# Sheet2_3.net
KiCad netlist of a schematic drawn in Altium Designer
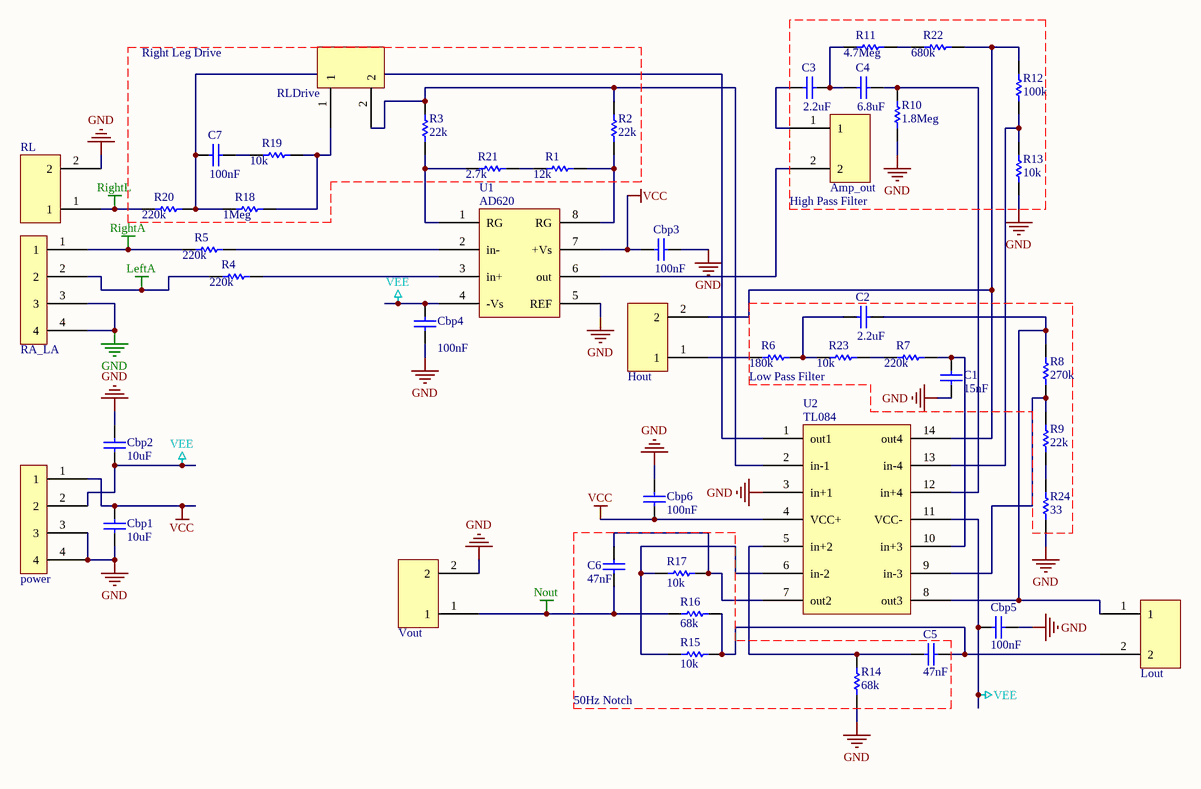
[diagram p0: Sheet2.~(3).SchDoc]

(export (version "E")
  (design (tool "Eeschema 10.0.6"))
  (components
    (comp (ref "Amp_out") (value "port") (footprint "pinheader") (libsource (lib "") (part "port_2")))
    (comp (ref "C1")
      (value "15nF")
      (footprint "cap")
      (description "Capacitor")
      (fields (field (name "Comment") "Cap") (field (name "PUBLISHER") "Altium Limited"))
      (libsource (lib "Miscellaneous Devices") (part "Cap"))
    )
    (comp (ref "C2")
      (value "2.2uF")
      (footprint "cap")
      (description "Capacitor")
      (fields (field (name "Comment") "Cap") (field (name "PUBLISHER") "Altium Limited"))
      (libsource (lib "Miscellaneous Devices") (part "Cap"))
    )
    (comp (ref "C3")
      (value "2.2uF")
      (footprint "cap")
      (description "Capacitor")
      (fields (field (name "Comment") "Cap") (field (name "PUBLISHER") "Altium Limited"))
      (libsource (lib "Miscellaneous Devices") (part "Cap"))
    )
    (comp (ref "C4")
      (value "6.8uF")
      (footprint "cap")
      (description "Capacitor")
      (fields (field (name "Comment") "Cap") (field (name "PUBLISHER") "Altium Limited"))
      (libsource (lib "Miscellaneous Devices") (part "Cap"))
    )
    (comp (ref "C5")
      (value "47nF")
      (footprint "cap")
      (description "Capacitor")
      (fields (field (name "Comment") "Cap") (field (name "PUBLISHER") "Altium Limited"))
      (libsource (lib "Miscellaneous Devices") (part "Cap"))
    )
    (comp (ref "C6")
      (value "47nF")
      (footprint "cap")
      (description "Capacitor")
      (fields (field (name "Comment") "Cap") (field (name "PUBLISHER") "Altium Limited"))
      (libsource (lib "Miscellaneous Devices") (part "Cap"))
    )
    (comp (ref "C7")
      (value "100nF")
      (footprint "cap")
      (description "Capacitor")
      (fields (field (name "Comment") "Cap") (field (name "PUBLISHER") "Altium Limited"))
      (libsource (lib "Miscellaneous Devices") (part "Cap"))
    )
    (comp (ref "Cbp1")
      (value "10uF")
      (footprint "cap")
      (description "Capacitor")
      (fields (field (name "Comment") "Cap") (field (name "PUBLISHER") "Altium Limited"))
      (libsource (lib "Miscellaneous Devices") (part "Cap"))
    )
    (comp (ref "Cbp2")
      (value "10uF")
      (footprint "cap")
      (description "Capacitor")
      (fields (field (name "Comment") "Cap") (field (name "PUBLISHER") "Altium Limited"))
      (libsource (lib "Miscellaneous Devices") (part "Cap"))
    )
    (comp (ref "Cbp3")
      (value "100nF")
      (footprint "cap")
      (description "Capacitor")
      (fields (field (name "Comment") "Cap") (field (name "PUBLISHER") "Altium Limited"))
      (libsource (lib "Miscellaneous Devices") (part "Cap"))
    )
    (comp (ref "Cbp4")
      (value "100nF")
      (footprint "cap")
      (description "Capacitor")
      (fields (field (name "Comment") "Cap") (field (name "PUBLISHER") "Altium Limited"))
      (libsource (lib "Miscellaneous Devices") (part "Cap"))
    )
    (comp (ref "Cbp5")
      (value "100nF")
      (footprint "cap")
      (description "Capacitor")
      (fields (field (name "Comment") "Cap") (field (name "PUBLISHER") "Altium Limited"))
      (libsource (lib "Miscellaneous Devices") (part "Cap"))
    )
    (comp (ref "Cbp6")
      (value "100nF")
      (footprint "cap")
      (description "Capacitor")
      (fields (field (name "Comment") "Cap") (field (name "PUBLISHER") "Altium Limited"))
      (libsource (lib "Miscellaneous Devices") (part "Cap"))
    )
    (comp (ref "Hout") (value "port") (footprint "pinheader") (libsource (lib "Schlib1") (part "port")))
    (comp (ref "Lout") (value "port") (footprint "pinheader") (libsource (lib "") (part "port_2")))
    (comp (ref "power") (value "pin4") (footprint "PINHEADER4") (libsource (lib "Schlib1") (part "pin4")))
    (comp (ref "R1")
      (value "12k")
      (footprint "res")
      (description "Semiconductor Resistor")
      (fields (field (name "Comment") "Res Semi") (field (name "PUBLISHER") "Altium Limited"))
      (libsource (lib "Miscellaneous Devices") (part "Res Semi"))
    )
    (comp (ref "R2")
      (value "22k")
      (footprint "res")
      (description "Semiconductor Resistor")
      (fields (field (name "Comment") "Res Semi") (field (name "PUBLISHER") "Altium Limited"))
      (libsource (lib "Miscellaneous Devices") (part "Res Semi"))
    )
    (comp (ref "R3")
      (value "22k")
      (footprint "res")
      (description "Semiconductor Resistor")
      (fields (field (name "Comment") "Res Semi") (field (name "PUBLISHER") "Altium Limited"))
      (libsource (lib "Miscellaneous Devices") (part "Res Semi"))
    )
    (comp (ref "R4")
      (value "220k")
      (footprint "res")
      (description "Semiconductor Resistor")
      (fields (field (name "Comment") "Res Semi") (field (name "PUBLISHER") "Altium Limited"))
      (libsource (lib "Miscellaneous Devices") (part "Res Semi"))
    )
    (comp (ref "R5")
      (value "220k")
      (footprint "res")
      (description "Semiconductor Resistor")
      (fields (field (name "Comment") "Res Semi") (field (name "PUBLISHER") "Altium Limited"))
      (libsource (lib "Miscellaneous Devices") (part "Res Semi"))
    )
    (comp (ref "R6")
      (value "180k")
      (footprint "res")
      (description "Semiconductor Resistor")
      (fields (field (name "Comment") "Res Semi") (field (name "PUBLISHER") "Altium Limited"))
      (libsource (lib "Miscellaneous Devices") (part "Res Semi"))
    )
    (comp (ref "R7")
      (value "220k")
      (footprint "res")
      (description "Semiconductor Resistor")
      (fields (field (name "Comment") "Res Semi") (field (name "PUBLISHER") "Altium Limited"))
      (libsource (lib "Miscellaneous Devices") (part "Res Semi"))
    )
    (comp (ref "R8")
      (value "270k")
      (footprint "res")
      (description "Semiconductor Resistor")
      (fields (field (name "Comment") "Res Semi") (field (name "PUBLISHER") "Altium Limited"))
      (libsource (lib "Miscellaneous Devices") (part "Res Semi"))
    )
    (comp (ref "R9")
      (value "22k")
      (footprint "res")
      (description "Semiconductor Resistor")
      (fields (field (name "Comment") "Res Semi") (field (name "PUBLISHER") "Altium Limited"))
      (libsource (lib "Miscellaneous Devices") (part "Res Semi"))
    )
    (comp (ref "R10")
      (value "1.8Meg")
      (footprint "res")
      (description "Semiconductor Resistor")
      (fields (field (name "Comment") "Res Semi") (field (name "PUBLISHER") "Altium Limited"))
      (libsource (lib "Miscellaneous Devices") (part "Res Semi"))
    )
    (comp (ref "R11")
      (value "4.7Meg")
      (footprint "res")
      (description "Semiconductor Resistor")
      (fields (field (name "Comment") "Res Semi") (field (name "PUBLISHER") "Altium Limited"))
      (libsource (lib "Miscellaneous Devices") (part "Res Semi"))
    )
    (comp (ref "R12")
      (value "100k")
      (footprint "res")
      (description "Semiconductor Resistor")
      (fields (field (name "Comment") "Res Semi") (field (name "PUBLISHER") "Altium Limited"))
      (libsource (lib "Miscellaneous Devices") (part "Res Semi"))
    )
    (comp (ref "R13")
      (value "10k")
      (footprint "res")
      (description "Semiconductor Resistor")
      (fields (field (name "Comment") "Res Semi") (field (name "PUBLISHER") "Altium Limited"))
      (libsource (lib "Miscellaneous Devices") (part "Res Semi"))
    )
    (comp (ref "R14")
      (value "68k")
      (footprint "res")
      (description "Semiconductor Resistor")
      (fields (field (name "Comment") "Res Semi") (field (name "PUBLISHER") "Altium Limited"))
      (libsource (lib "Miscellaneous Devices") (part "Res Semi"))
    )
    (comp (ref "R15")
      (value "10k")
      (footprint "res")
      (description "Semiconductor Resistor")
      (fields (field (name "Comment") "Res Semi") (field (name "PUBLISHER") "Altium Limited"))
      (libsource (lib "Miscellaneous Devices") (part "Res Semi"))
    )
    (comp (ref "R16")
      (value "68k")
      (footprint "res")
      (description "Semiconductor Resistor")
      (fields (field (name "Comment") "Res Semi") (field (name "PUBLISHER") "Altium Limited"))
      (libsource (lib "Miscellaneous Devices") (part "Res Semi"))
    )
    (comp (ref "R17")
      (value "10k")
      (footprint "res")
      (description "Semiconductor Resistor")
      (fields (field (name "Comment") "Res Semi") (field (name "PUBLISHER") "Altium Limited"))
      (libsource (lib "Miscellaneous Devices") (part "Res Semi"))
    )
    (comp (ref "R18")
      (value "1Meg")
      (footprint "res")
      (description "Semiconductor Resistor")
      (fields (field (name "Comment") "Res Semi") (field (name "PUBLISHER") "Altium Limited"))
      (libsource (lib "Miscellaneous Devices") (part "Res Semi"))
    )
    (comp (ref "R19")
      (value "10k")
      (footprint "res")
      (description "Semiconductor Resistor")
      (fields (field (name "Comment") "Res Semi") (field (name "PUBLISHER") "Altium Limited"))
      (libsource (lib "Miscellaneous Devices") (part "Res Semi"))
    )
    (comp (ref "R20")
      (value "220k")
      (footprint "res")
      (description "Semiconductor Resistor")
      (fields (field (name "Comment") "Res Semi") (field (name "PUBLISHER") "Altium Limited"))
      (libsource (lib "Miscellaneous Devices") (part "Res Semi"))
    )
    (comp (ref "R21")
      (value "2.7k")
      (footprint "res")
      (description "Semiconductor Resistor")
      (fields (field (name "Comment") "Res Semi") (field (name "PUBLISHER") "Altium Limited"))
      (libsource (lib "Miscellaneous Devices") (part "Res Semi"))
    )
    (comp (ref "R22")
      (value "680k")
      (footprint "res")
      (description "Semiconductor Resistor")
      (fields (field (name "Comment") "Res Semi") (field (name "PUBLISHER") "Altium Limited"))
      (libsource (lib "Miscellaneous Devices") (part "Res Semi"))
    )
    (comp (ref "R23")
      (value "10k")
      (footprint "res")
      (description "Semiconductor Resistor")
      (fields (field (name "Comment") "Res Semi") (field (name "PUBLISHER") "Altium Limited"))
      (libsource (lib "Miscellaneous Devices") (part "Res Semi"))
    )
    (comp (ref "R24")
      (value "33")
      (footprint "res")
      (description "Semiconductor Resistor")
      (fields (field (name "Comment") "Res Semi") (field (name "PUBLISHER") "Altium Limited"))
      (libsource (lib "Miscellaneous Devices") (part "Res Semi"))
    )
    (comp (ref "RA_LA") (value "pin4") (footprint "PINHEADER4") (libsource (lib "Schlib1") (part "pin4")))
    (comp (ref "RL") (value "port") (footprint "pinheader") (libsource (lib "Schlib1") (part "port")))
    (comp (ref "RLDrive") (value "port") (footprint "pinheader") (libsource (lib "") (part "port_1")))
    (comp (ref "U1") (value "AD620") (footprint "AD620") (libsource (lib "Schlib1") (part "AD620")))
    (comp (ref "U2") (value "TL084") (footprint "TL084") (libsource (lib "Schlib1") (part "TL084")))
    (comp (ref "Vout") (value "port") (footprint "pinheader") (libsource (lib "Schlib1") (part "port")))
  )
  (nets
    (net (code "1") (name "GND") (class "Default")
      (node (ref "C1") (pin "1") (pinfunction "1_1") (pintype "passive"))
      (node (ref "Cbp1") (pin "1") (pinfunction "1_1") (pintype "passive"))
      (node (ref "Cbp2") (pin "2") (pinfunction "2_2") (pintype "passive"))
      (node (ref "Cbp3") (pin "2") (pinfunction "2_2") (pintype "passive"))
      (node (ref "Cbp4") (pin "1") (pinfunction "1_1") (pintype "passive"))
      (node (ref "Cbp5") (pin "1") (pinfunction "1_1") (pintype "passive"))
      (node (ref "Cbp6") (pin "1") (pinfunction "1_1") (pintype "passive"))
      (node (ref "R10") (pin "1") (pinfunction "1_1") (pintype "passive"))
      (node (ref "R13") (pin "1") (pinfunction "1_1") (pintype "passive"))
      (node (ref "R14") (pin "1") (pinfunction "1_1") (pintype "passive"))
      (node (ref "R24") (pin "1") (pinfunction "1_1") (pintype "passive"))
      (node (ref "RA_LA") (pin "3") (pinfunction "3_3") (pintype "passive"))
      (node (ref "RA_LA") (pin "4") (pinfunction "4_4") (pintype "passive"))
      (node (ref "RL") (pin "2") (pinfunction "2_2") (pintype "passive"))
      (node (ref "U1") (pin "5") (pinfunction "REF_5") (pintype "passive"))
      (node (ref "U2") (pin "3") (pinfunction "in+1_3") (pintype "passive"))
      (node (ref "Vout") (pin "2") (pinfunction "2_2") (pintype "passive"))
      (node (ref "power") (pin "3") (pinfunction "3_3") (pintype "passive"))
      (node (ref "power") (pin "4") (pinfunction "4_4") (pintype "passive"))
    )
    (net (code "2") (name "LeftA") (class "Default")
      (node (ref "R4") (pin "1") (pinfunction "1_1") (pintype "passive"))
      (node (ref "RA_LA") (pin "2") (pinfunction "2_2") (pintype "passive"))
    )
    (net (code "3") (name "Net-(Amp_out-Pad1)") (class "Default")
      (node (ref "Amp_out") (pin "1") (pinfunction "1_1") (pintype "passive"))
      (node (ref "C3") (pin "1") (pinfunction "1_1") (pintype "passive"))
    )
    (net (code "4") (name "Net-(C2-Pad1)") (class "Default")
      (node (ref "C2") (pin "1") (pinfunction "1_1") (pintype "passive"))
      (node (ref "R23") (pin "1") (pinfunction "1_1") (pintype "passive"))
      (node (ref "R6") (pin "2") (pinfunction "2_2") (pintype "passive"))
    )
    (net (code "5") (name "Net-(C3-Pad2)") (class "Default")
      (node (ref "C3") (pin "2") (pinfunction "2_2") (pintype "passive"))
      (node (ref "C4") (pin "1") (pinfunction "1_1") (pintype "passive"))
      (node (ref "R11") (pin "1") (pinfunction "1_1") (pintype "passive"))
    )
    (net (code "6") (name "Net-(C5-Pad1)") (class "Default")
      (node (ref "C5") (pin "1") (pinfunction "1_1") (pintype "passive"))
      (node (ref "Lout") (pin "2") (pinfunction "2_2") (pintype "passive"))
      (node (ref "R15") (pin "2") (pinfunction "2_2") (pintype "passive"))
      (node (ref "R16") (pin "2") (pinfunction "2_2") (pintype "passive"))
    )
    (net (code "7") (name "Net-(C7-Pad2)") (class "Default")
      (node (ref "C7") (pin "2") (pinfunction "2_2") (pintype "passive"))
      (node (ref "R19") (pin "1") (pinfunction "1_1") (pintype "passive"))
    )
    (net (code "8") (name "Net-(Hout-Pad1)") (class "Default")
      (node (ref "Hout") (pin "1") (pinfunction "1_1") (pintype "passive"))
      (node (ref "R6") (pin "1") (pinfunction "1_1") (pintype "passive"))
    )
    (net (code "9") (name "Net-(R1-Pad1)") (class "Default")
      (node (ref "R1") (pin "1") (pinfunction "1_1") (pintype "passive"))
      (node (ref "R21") (pin "2") (pinfunction "2_2") (pintype "passive"))
    )
    (net (code "10") (name "Net-(R1-Pad2)") (class "Default")
      (node (ref "R1") (pin "2") (pinfunction "2_2") (pintype "passive"))
      (node (ref "R2") (pin "1") (pinfunction "1_1") (pintype "passive"))
      (node (ref "U1") (pin "8") (pinfunction "RG_8") (pintype "passive"))
    )
    (net (code "11") (name "Net-(R11-Pad2)") (class "Default")
      (node (ref "R11") (pin "2") (pinfunction "2_2") (pintype "passive"))
      (node (ref "R22") (pin "1") (pinfunction "1_1") (pintype "passive"))
    )
    (net (code "12") (name "Net-(R18-Pad2)") (class "Default")
      (node (ref "R18") (pin "2") (pinfunction "2_2") (pintype "passive"))
      (node (ref "R19") (pin "2") (pinfunction "2_2") (pintype "passive"))
      (node (ref "RLDrive") (pin "1") (pinfunction "1_1") (pintype "passive"))
    )
    (net (code "13") (name "Net-(R21-Pad1)") (class "Default")
      (node (ref "R21") (pin "1") (pinfunction "1_1") (pintype "passive"))
      (node (ref "R3") (pin "2") (pinfunction "2_2") (pintype "passive"))
      (node (ref "U1") (pin "1") (pinfunction "RG_1") (pintype "passive"))
    )
    (net (code "14") (name "Net-(R23-Pad2)") (class "Default")
      (node (ref "R23") (pin "2") (pinfunction "2_2") (pintype "passive"))
      (node (ref "R7") (pin "1") (pinfunction "1_1") (pintype "passive"))
    )
    (net (code "15") (name "Net-(R24-Pad2)") (class "Default")
      (node (ref "R24") (pin "2") (pinfunction "2_2") (pintype "passive"))
      (node (ref "R9") (pin "1") (pinfunction "1_1") (pintype "passive"))
    )
    (net (code "16") (name "Net-(U1-in+)") (class "Default")
      (node (ref "R4") (pin "2") (pinfunction "2_2") (pintype "passive"))
      (node (ref "U1") (pin "3") (pinfunction "in+_3") (pintype "passive"))
    )
    (net (code "17") (name "Net-(U1-in-)") (class "Default")
      (node (ref "R5") (pin "2") (pinfunction "2_2") (pintype "passive"))
      (node (ref "U1") (pin "2") (pinfunction "in-_2") (pintype "passive"))
    )
    (net (code "18") (name "Net-(U1-out)") (class "Default")
      (node (ref "Amp_out") (pin "2") (pinfunction "2_2") (pintype "passive"))
      (node (ref "U1") (pin "6") (pinfunction "out_6") (pintype "passive"))
    )
    (net (code "19") (name "Net-(U2-in+2)") (class "Default")
      (node (ref "C5") (pin "2") (pinfunction "2_2") (pintype "passive"))
      (node (ref "R14") (pin "2") (pinfunction "2_2") (pintype "passive"))
      (node (ref "U2") (pin "5") (pinfunction "in+2_5") (pintype "passive"))
    )
    (net (code "20") (name "Net-(U2-in+3)") (class "Default")
      (node (ref "C1") (pin "2") (pinfunction "2_2") (pintype "passive"))
      (node (ref "R7") (pin "2") (pinfunction "2_2") (pintype "passive"))
      (node (ref "U2") (pin "10") (pinfunction "in+3_10") (pintype "passive"))
    )
    (net (code "21") (name "Net-(U2-in+4)") (class "Default")
      (node (ref "C4") (pin "2") (pinfunction "2_2") (pintype "passive"))
      (node (ref "R10") (pin "2") (pinfunction "2_2") (pintype "passive"))
      (node (ref "U2") (pin "12") (pinfunction "in+4_12") (pintype "passive"))
    )
    (net (code "22") (name "Net-(U2-in-1)") (class "Default")
      (node (ref "R2") (pin "2") (pinfunction "2_2") (pintype "passive"))
      (node (ref "R3") (pin "1") (pinfunction "1_1") (pintype "passive"))
      (node (ref "RLDrive") (pin "2") (pinfunction "2_2") (pintype "passive"))
      (node (ref "U2") (pin "2") (pinfunction "in-1_2") (pintype "passive"))
    )
    (net (code "23") (name "Net-(U2-in-2)") (class "Default")
      (node (ref "R15") (pin "1") (pinfunction "1_1") (pintype "passive"))
      (node (ref "R17") (pin "1") (pinfunction "1_1") (pintype "passive"))
      (node (ref "U2") (pin "6") (pinfunction "in-2_6") (pintype "passive"))
    )
    (net (code "24") (name "Net-(U2-in-3)") (class "Default")
      (node (ref "R8") (pin "1") (pinfunction "1_1") (pintype "passive"))
      (node (ref "R9") (pin "2") (pinfunction "2_2") (pintype "passive"))
      (node (ref "U2") (pin "9") (pinfunction "in-3_9") (pintype "passive"))
    )
    (net (code "25") (name "Net-(U2-in-4)") (class "Default")
      (node (ref "R12") (pin "1") (pinfunction "1_1") (pintype "passive"))
      (node (ref "R13") (pin "2") (pinfunction "2_2") (pintype "passive"))
      (node (ref "U2") (pin "13") (pinfunction "in-4_13") (pintype "passive"))
    )
    (net (code "26") (name "Net-(U2-out1)") (class "Default")
      (node (ref "C7") (pin "1") (pinfunction "1_1") (pintype "passive"))
      (node (ref "R18") (pin "1") (pinfunction "1_1") (pintype "passive"))
      (node (ref "R20") (pin "2") (pinfunction "2_2") (pintype "passive"))
      (node (ref "U2") (pin "1") (pinfunction "out1_1") (pintype "passive"))
    )
    (net (code "27") (name "Net-(U2-out2)") (class "Default")
      (node (ref "C6") (pin "2") (pinfunction "2_2") (pintype "passive"))
      (node (ref "R17") (pin "2") (pinfunction "2_2") (pintype "passive"))
      (node (ref "U2") (pin "7") (pinfunction "out2_7") (pintype "passive"))
    )
    (net (code "28") (name "Net-(U2-out3)") (class "Default")
      (node (ref "C2") (pin "2") (pinfunction "2_2") (pintype "passive"))
      (node (ref "Lout") (pin "1") (pinfunction "1_1") (pintype "passive"))
      (node (ref "R8") (pin "2") (pinfunction "2_2") (pintype "passive"))
      (node (ref "U2") (pin "8") (pinfunction "out3_8") (pintype "passive"))
    )
    (net (code "29") (name "Net-(U2-out4)") (class "Default")
      (node (ref "Hout") (pin "2") (pinfunction "2_2") (pintype "passive"))
      (node (ref "R12") (pin "2") (pinfunction "2_2") (pintype "passive"))
      (node (ref "R22") (pin "2") (pinfunction "2_2") (pintype "passive"))
      (node (ref "U2") (pin "14") (pinfunction "out4_14") (pintype "passive"))
    )
    (net (code "30") (name "Nout") (class "Default")
      (node (ref "C6") (pin "1") (pinfunction "1_1") (pintype "passive"))
      (node (ref "R16") (pin "1") (pinfunction "1_1") (pintype "passive"))
      (node (ref "Vout") (pin "1") (pinfunction "1_1") (pintype "passive"))
    )
    (net (code "31") (name "RightA") (class "Default")
      (node (ref "R5") (pin "1") (pinfunction "1_1") (pintype "passive"))
      (node (ref "RA_LA") (pin "1") (pinfunction "1_1") (pintype "passive"))
    )
    (net (code "32") (name "RightL") (class "Default")
      (node (ref "R20") (pin "1") (pinfunction "1_1") (pintype "passive"))
      (node (ref "RL") (pin "1") (pinfunction "1_1") (pintype "passive"))
    )
    (net (code "33") (name "VCC") (class "Default")
      (node (ref "Cbp1") (pin "2") (pinfunction "2_2") (pintype "passive"))
      (node (ref "Cbp3") (pin "1") (pinfunction "1_1") (pintype "passive"))
      (node (ref "Cbp6") (pin "2") (pinfunction "2_2") (pintype "passive"))
      (node (ref "U1") (pin "7") (pinfunction "+Vs_7") (pintype "passive"))
      (node (ref "U2") (pin "4") (pinfunction "VCC+_4") (pintype "passive"))
      (node (ref "power") (pin "1") (pinfunction "1_1") (pintype "passive"))
    )
    (net (code "34") (name "VEE") (class "Default")
      (node (ref "Cbp2") (pin "1") (pinfunction "1_1") (pintype "passive"))
      (node (ref "Cbp4") (pin "2") (pinfunction "2_2") (pintype "passive"))
      (node (ref "Cbp5") (pin "2") (pinfunction "2_2") (pintype "passive"))
      (node (ref "U1") (pin "4") (pinfunction "-Vs_4") (pintype "passive"))
      (node (ref "U2") (pin "11") (pinfunction "VCC-_11") (pintype "passive"))
      (node (ref "power") (pin "2") (pinfunction "2_2") (pintype "passive"))
    )
  )
)
